# Capacitive_touch.net
KiCad netlist of a schematic drawn in Altium Designer
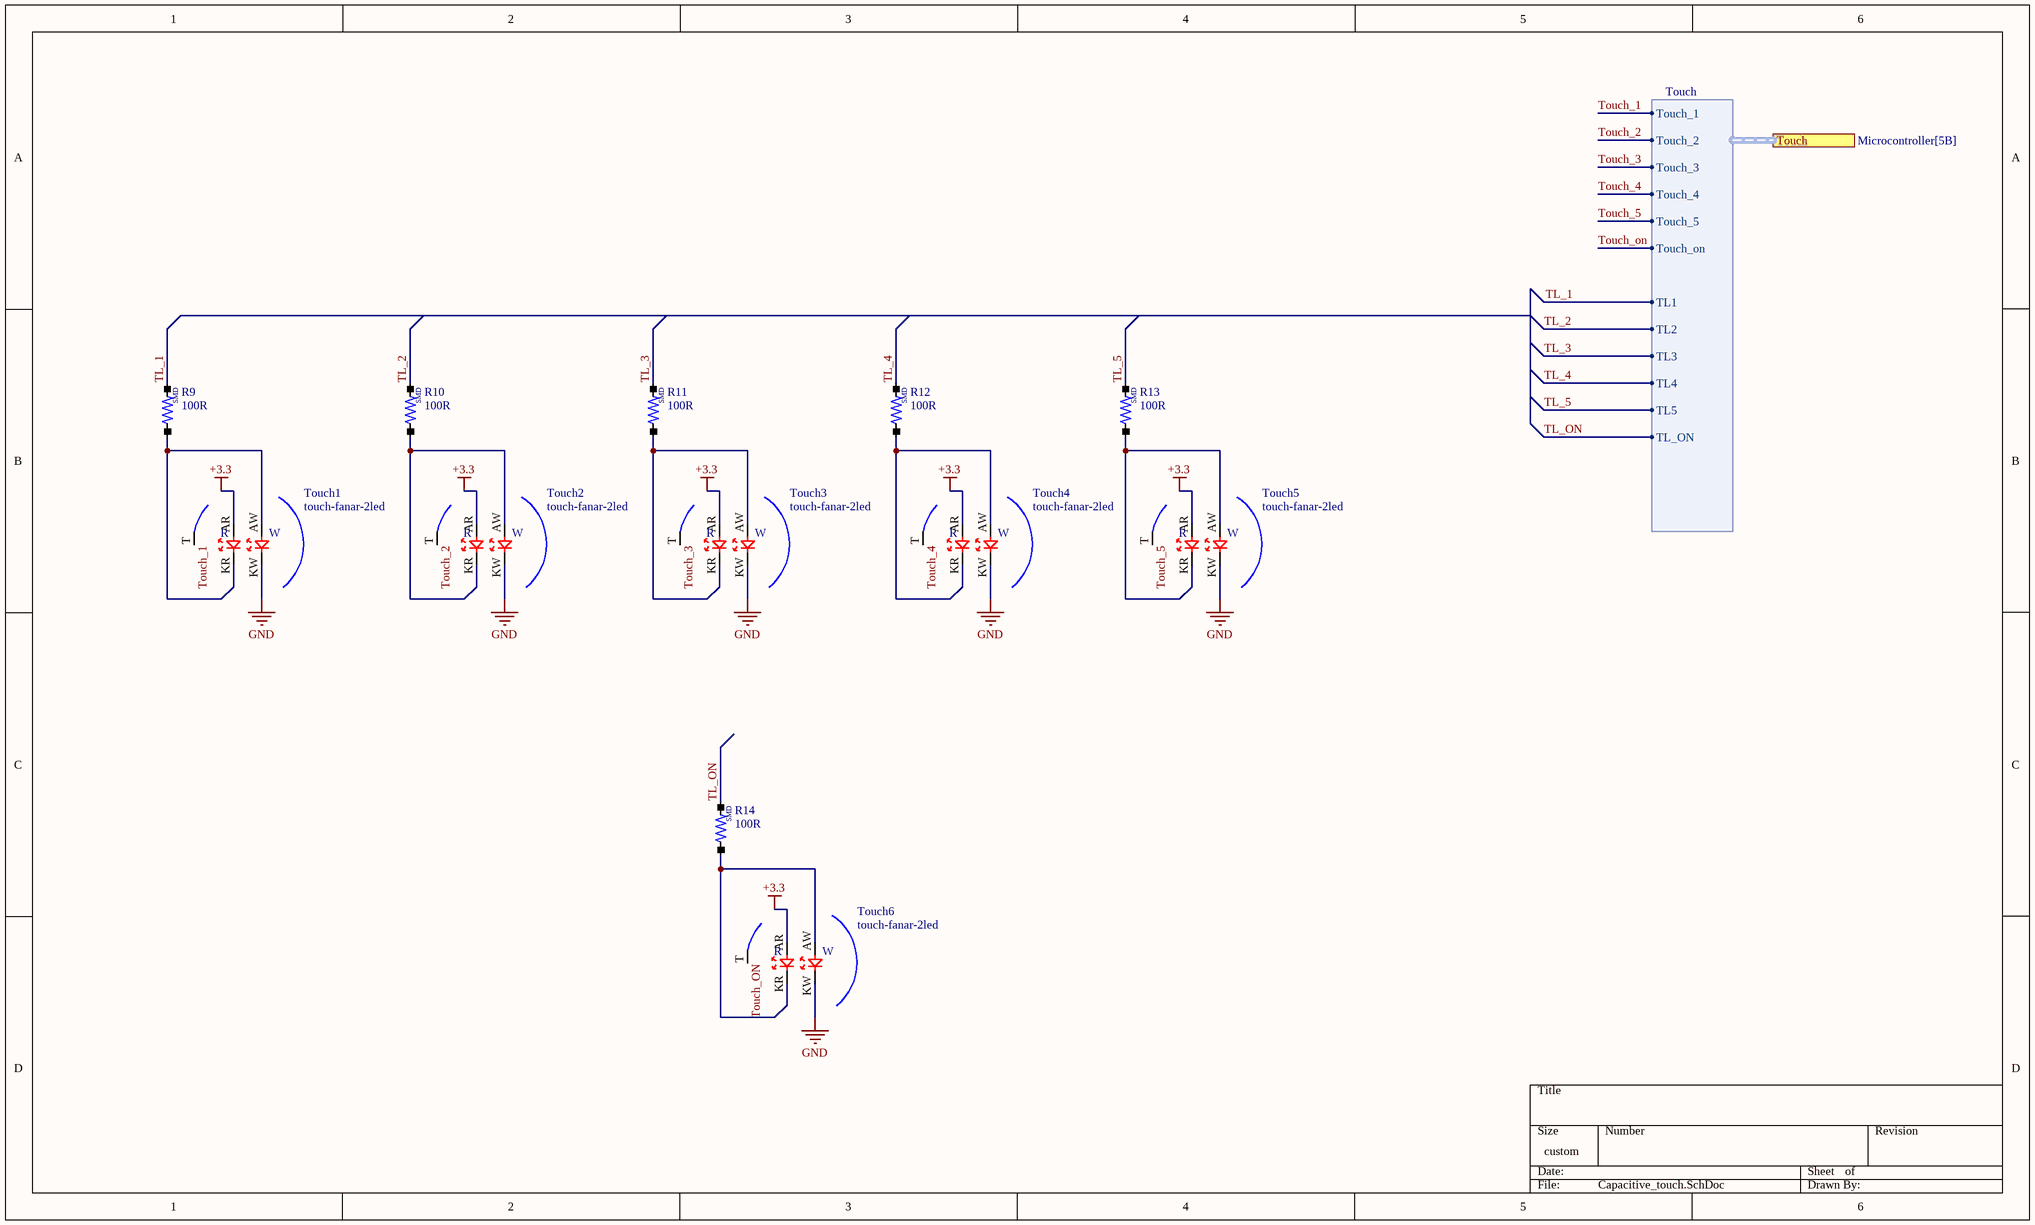
[diagram p0: Capacitive_touch.SchDoc]

(export (version "E")
  (design (tool "Eeschema 10.0.6"))
  (components
    (comp (ref "R9") (value "100R") (footprint "RES/0603") (libsource (lib "kave-eng-pro") (part "RES/SMD")))
    (comp (ref "R10") (value "100R") (footprint "RES/0603") (libsource (lib "kave-eng-pro") (part "RES/SMD")))
    (comp (ref "R11") (value "100R") (footprint "RES/0603") (libsource (lib "kave-eng-pro") (part "RES/SMD")))
    (comp (ref "R12") (value "100R") (footprint "RES/0603") (libsource (lib "kave-eng-pro") (part "RES/SMD")))
    (comp (ref "R13") (value "100R") (footprint "RES/0603") (libsource (lib "kave-eng-pro") (part "RES/SMD")))
    (comp (ref "R14") (value "100R") (footprint "RES/0603") (libsource (lib "kave-eng-pro") (part "RES/SMD")))
    (comp (ref "Touch1")
      (value "touch-fanar-2led")
      (footprint "fanar-touch-2led")
      (libsource (lib "kave-eng-pro") (part "touch-fanar-2led"))
    )
    (comp (ref "Touch2")
      (value "touch-fanar-2led")
      (footprint "fanar-touch-2led")
      (libsource (lib "kave-eng-pro") (part "touch-fanar-2led"))
    )
    (comp (ref "Touch3")
      (value "touch-fanar-2led")
      (footprint "fanar-touch-2led")
      (libsource (lib "kave-eng-pro") (part "touch-fanar-2led"))
    )
    (comp (ref "Touch4")
      (value "touch-fanar-2led")
      (footprint "fanar-touch-2led")
      (libsource (lib "kave-eng-pro") (part "touch-fanar-2led"))
    )
    (comp (ref "Touch5")
      (value "touch-fanar-2led")
      (footprint "fanar-touch-2led")
      (libsource (lib "kave-eng-pro") (part "touch-fanar-2led"))
    )
    (comp (ref "Touch6")
      (value "touch-fanar-2led")
      (footprint "fanar-touch-2led")
      (libsource (lib "kave-eng-pro") (part "touch-fanar-2led"))
    )
  )
  (nets
    (net (code "2") (name "+3.3") (class "Default")
      (node (ref "Touch1") (pin "AR") (pintype "passive"))
      (node (ref "Touch2") (pin "AR") (pintype "passive"))
      (node (ref "Touch3") (pin "AR") (pintype "passive"))
      (node (ref "Touch4") (pin "AR") (pintype "passive"))
      (node (ref "Touch5") (pin "AR") (pintype "passive"))
      (node (ref "Touch6") (pin "AR") (pintype "passive"))
    )
    (net (code "3") (name "/TL_1") (class "Default")
      (node (ref "R9") (pin "2") (pinfunction "2_2") (pintype "passive"))
    )
    (net (code "4") (name "/TL_2") (class "Default")
      (node (ref "R10") (pin "2") (pinfunction "2_2") (pintype "passive"))
    )
    (net (code "5") (name "/TL_3") (class "Default")
      (node (ref "R11") (pin "2") (pinfunction "2_2") (pintype "passive"))
    )
    (net (code "6") (name "/TL_4") (class "Default")
      (node (ref "R12") (pin "2") (pinfunction "2_2") (pintype "passive"))
    )
    (net (code "7") (name "/TL_5") (class "Default")
      (node (ref "R13") (pin "2") (pinfunction "2_2") (pintype "passive"))
    )
    (net (code "8") (name "/TL_ON") (class "Default")
      (node (ref "R14") (pin "2") (pinfunction "2_2") (pintype "passive"))
    )
    (net (code "9") (name "/Touch_1") (class "Default") (node (ref "Touch1") (pin "T") (pintype "passive")))
    (net (code "10") (name "/Touch_2") (class "Default") (node (ref "Touch2") (pin "T") (pintype "passive")))
    (net (code "11") (name "/Touch_3") (class "Default") (node (ref "Touch3") (pin "T") (pintype "passive")))
    (net (code "12") (name "/Touch_4") (class "Default") (node (ref "Touch4") (pin "T") (pintype "passive")))
    (net (code "13") (name "/Touch_5") (class "Default") (node (ref "Touch5") (pin "T") (pintype "passive")))
    (net (code "14") (name "/Touch_ON") (class "Default") (node (ref "Touch6") (pin "T") (pintype "passive")))
    (net (code "17") (name "GND") (class "Default")
      (node (ref "Touch1") (pin "KW") (pintype "passive"))
      (node (ref "Touch2") (pin "KW") (pintype "passive"))
      (node (ref "Touch3") (pin "KW") (pintype "passive"))
      (node (ref "Touch4") (pin "KW") (pintype "passive"))
      (node (ref "Touch5") (pin "KW") (pintype "passive"))
      (node (ref "Touch6") (pin "KW") (pintype "passive"))
    )
    (net (code "18") (name "Net-(R9-Pad1)") (class "Default")
      (node (ref "R9") (pin "1") (pinfunction "1_1") (pintype "passive"))
      (node (ref "Touch1") (pin "AW") (pintype "passive"))
      (node (ref "Touch1") (pin "KR") (pintype "passive"))
    )
    (net (code "19") (name "Net-(R10-Pad1)") (class "Default")
      (node (ref "R10") (pin "1") (pinfunction "1_1") (pintype "passive"))
      (node (ref "Touch2") (pin "AW") (pintype "passive"))
      (node (ref "Touch2") (pin "KR") (pintype "passive"))
    )
    (net (code "20") (name "Net-(R11-Pad1)") (class "Default")
      (node (ref "R11") (pin "1") (pinfunction "1_1") (pintype "passive"))
      (node (ref "Touch3") (pin "AW") (pintype "passive"))
      (node (ref "Touch3") (pin "KR") (pintype "passive"))
    )
    (net (code "21") (name "Net-(R12-Pad1)") (class "Default")
      (node (ref "R12") (pin "1") (pinfunction "1_1") (pintype "passive"))
      (node (ref "Touch4") (pin "AW") (pintype "passive"))
      (node (ref "Touch4") (pin "KR") (pintype "passive"))
    )
    (net (code "22") (name "Net-(R13-Pad1)") (class "Default")
      (node (ref "R13") (pin "1") (pinfunction "1_1") (pintype "passive"))
      (node (ref "Touch5") (pin "AW") (pintype "passive"))
      (node (ref "Touch5") (pin "KR") (pintype "passive"))
    )
    (net (code "23") (name "Net-(R14-Pad1)") (class "Default")
      (node (ref "R14") (pin "1") (pinfunction "1_1") (pintype "passive"))
      (node (ref "Touch6") (pin "AW") (pintype "passive"))
      (node (ref "Touch6") (pin "KR") (pintype "passive"))
    )
  )
)
